# interface_dac_sma_feedback_2PS_LM317.net
KiCad netlist of a schematic drawn in EAGLE
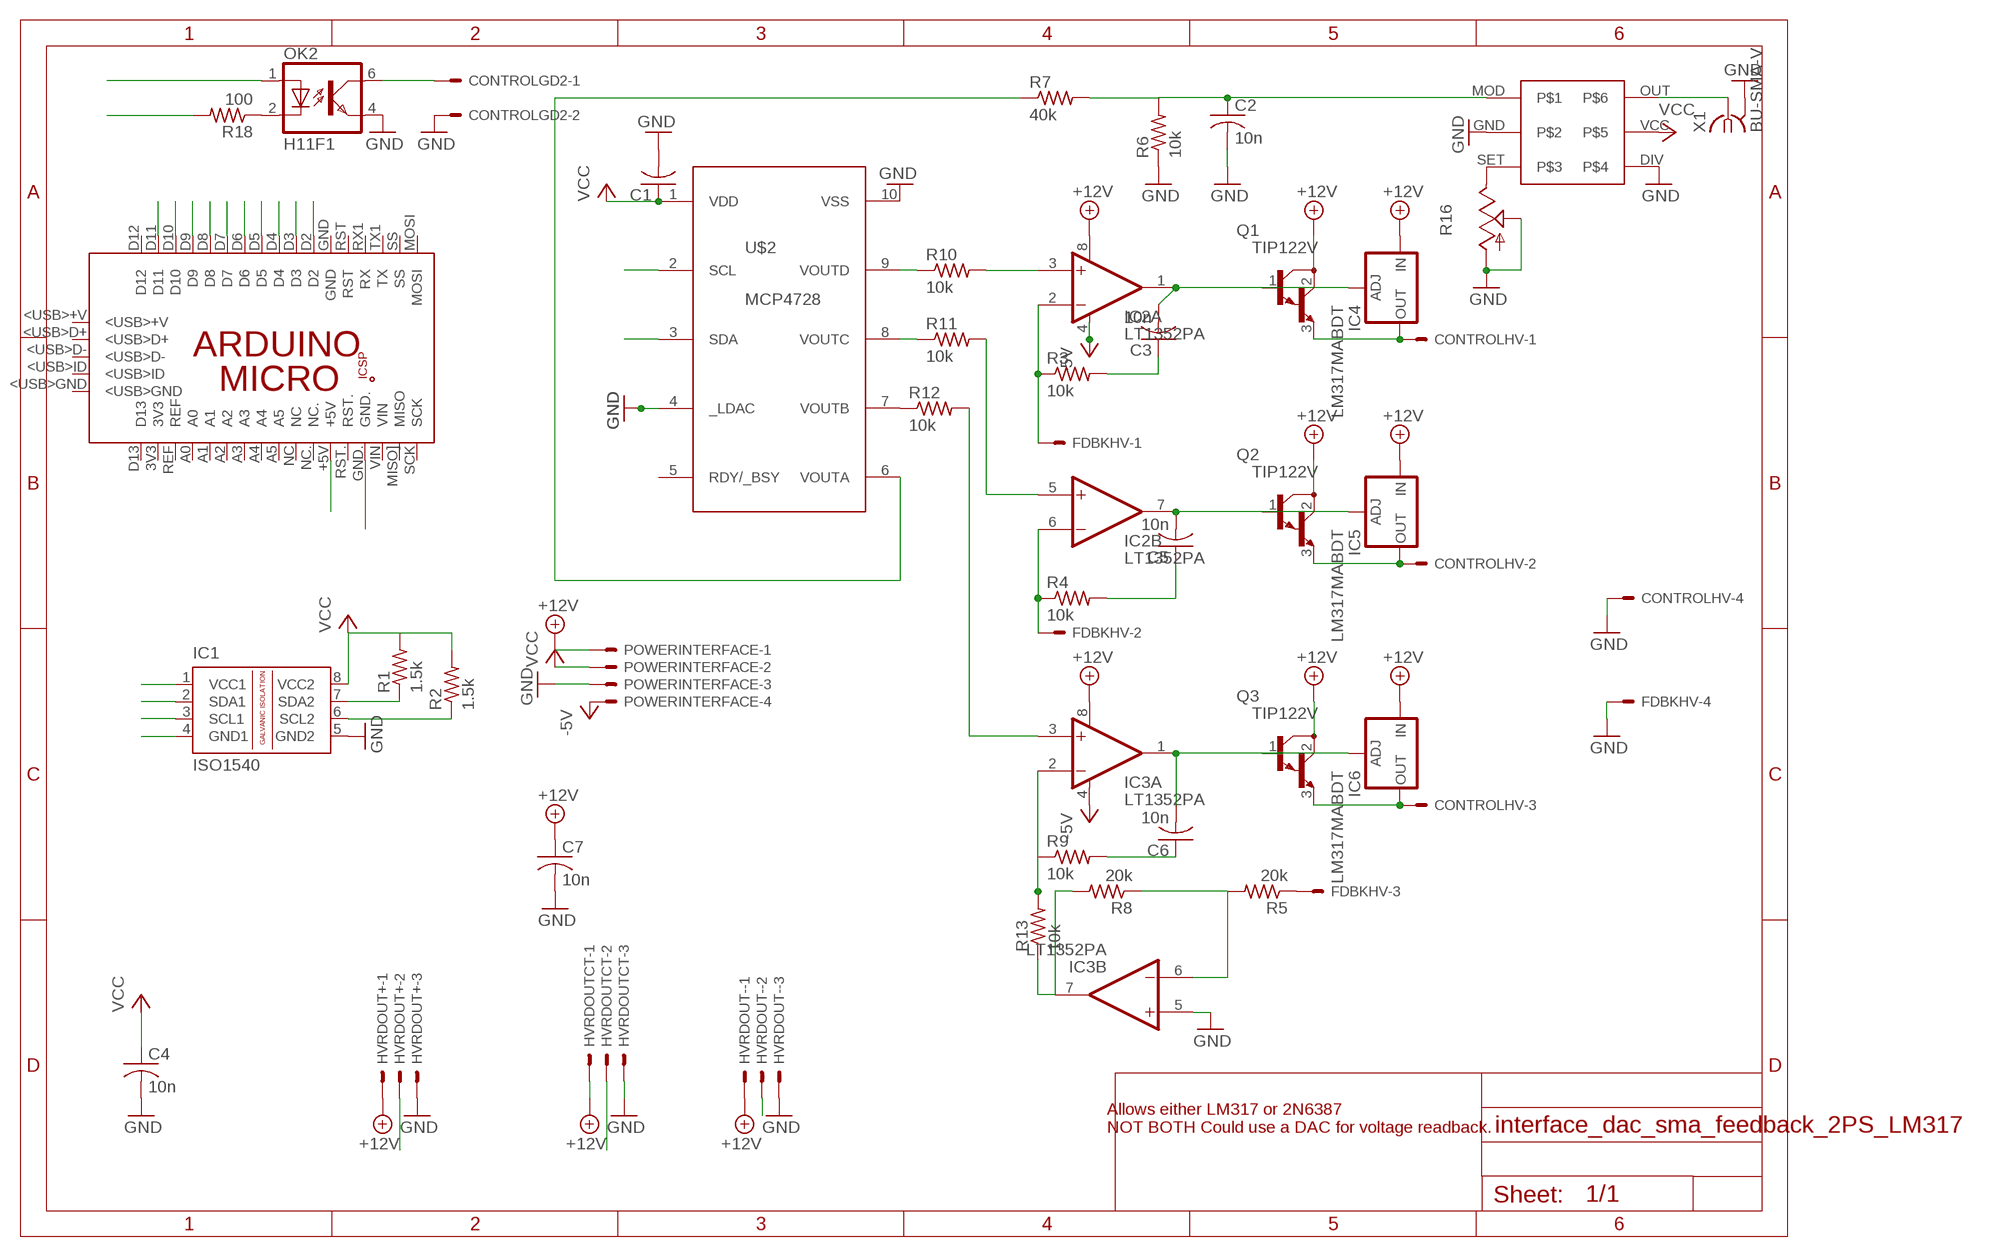
[diagram p0: schematic, sheet 1]

(export (version "E")
  (design (tool "Eeschema 10.0.6"))
  (components
    (comp (ref "C1")
      (value "C-US050-050X075")
      (footprint "eagle-import:C050-050X075")
      (libsource (lib "eagle-import") (part "C-US050-050X075"))
    )
    (comp (ref "C2")
      (value "10n")
      (footprint "eagle-import:C050-024X044")
      (libsource (lib "eagle-import") (part "resistor_C-US050-024X044"))
    )
    (comp (ref "C3")
      (value "10n")
      (footprint "eagle-import:C050-024X044")
      (libsource (lib "eagle-import") (part "resistor_C-US050-024X044"))
    )
    (comp (ref "C4")
      (value "10n")
      (footprint "eagle-import:C075-063X106")
      (libsource (lib "eagle-import") (part "resistor_C-US075-063X106"))
    )
    (comp (ref "C5")
      (value "10n")
      (footprint "eagle-import:C050-024X044")
      (libsource (lib "eagle-import") (part "resistor_C-US050-024X044"))
    )
    (comp (ref "C6")
      (value "10n")
      (footprint "eagle-import:C050-024X044")
      (libsource (lib "eagle-import") (part "resistor_C-US050-024X044"))
    )
    (comp (ref "C7")
      (value "10n")
      (footprint "eagle-import:C050-050X075")
      (libsource (lib "eagle-import") (part "resistor_C-US050-050X075"))
    )
    (comp (ref "CONTROLGD2")
      (value "KK-156-2")
      (footprint "eagle-import:KK-156-2")
      (libsource (lib "eagle-import") (part "KK-156-2"))
    )
    (comp (ref "CONTROLHV")
      (value "KK-156-4")
      (footprint "eagle-import:KK-156-4")
      (libsource (lib "eagle-import") (part "KK-156-4"))
    )
    (comp (ref "FDBKHV")
      (value "KK-156-4")
      (footprint "eagle-import:KK-156-4")
      (libsource (lib "eagle-import") (part "KK-156-4"))
    )
    (comp (ref "HVRDOUT+")
      (value "KK-156-3")
      (footprint "eagle-import:KK-156-3")
      (libsource (lib "eagle-import") (part "KK-156-3"))
    )
    (comp (ref "HVRDOUT-")
      (value "KK-156-3")
      (footprint "eagle-import:KK-156-3")
      (libsource (lib "eagle-import") (part "KK-156-3"))
    )
    (comp (ref "HVRDOUTCT")
      (value "KK-156-3")
      (footprint "eagle-import:KK-156-3")
      (libsource (lib "eagle-import") (part "KK-156-3"))
    )
    (comp (ref "IC1")
      (value "ISO1540")
      (footprint "eagle-import:DIL08")
      (libsource (lib "eagle-import") (part "ISO1540"))
    )
    (comp (ref "IC2")
      (value "LT1352PA")
      (footprint "eagle-import:DIL08")
      (libsource (lib "eagle-import") (part "LT1352PA"))
    )
    (comp (ref "IC3")
      (value "LT1352PA")
      (footprint "eagle-import:DIL08")
      (libsource (lib "eagle-import") (part "LT1352PA"))
    )
    (comp (ref "IC4")
      (value "LM317MABDT")
      (footprint "eagle-import:DPACK")
      (libsource (lib "eagle-import") (part "v-reg_LM317?MABDT"))
    )
    (comp (ref "IC5")
      (value "LM317MABDT")
      (footprint "eagle-import:DPACK")
      (libsource (lib "eagle-import") (part "v-reg_LM317?MABDT"))
    )
    (comp (ref "IC6")
      (value "LM317MABDT")
      (footprint "eagle-import:DPACK")
      (libsource (lib "eagle-import") (part "v-reg_LM317?MABDT"))
    )
    (comp (ref "OK2")
      (value "H11F1")
      (footprint "eagle-import:DIL05")
      (libsource (lib "eagle-import") (part "H11F1"))
    )
    (comp (ref "PCB1")
      (value "ARDUINO_MICRO")
      (footprint "eagle-import:ARDUINO_MICRO")
      (libsource (lib "eagle-import") (part "ARDUINO_MICRO"))
    )
    (comp (ref "POWERINTERFACE")
      (value "KK-156-4")
      (footprint "eagle-import:KK-156-4")
      (libsource (lib "eagle-import") (part "KK-156-4"))
    )
    (comp (ref "Q1")
      (value "TIP122V")
      (footprint "eagle-import:TO220V")
      (libsource (lib "eagle-import") (part "TIP122V"))
    )
    (comp (ref "Q2")
      (value "TIP122V")
      (footprint "eagle-import:TO220V")
      (libsource (lib "eagle-import") (part "TIP122V"))
    )
    (comp (ref "Q3")
      (value "TIP122V")
      (footprint "eagle-import:TO220V")
      (libsource (lib "eagle-import") (part "TIP122V"))
    )
    (comp (ref "R1")
      (value "1.5k")
      (footprint "eagle-import:0207_12")
      (libsource (lib "eagle-import") (part "resistor_R-US_0207/12"))
    )
    (comp (ref "R2")
      (value "1.5k")
      (footprint "eagle-import:0207_12")
      (libsource (lib "eagle-import") (part "resistor_R-US_0207/12"))
    )
    (comp (ref "R3")
      (value "10k")
      (footprint "eagle-import:0207_12")
      (libsource (lib "eagle-import") (part "resistor_R-US_0207/12"))
    )
    (comp (ref "R4")
      (value "10k")
      (footprint "eagle-import:0207_12")
      (libsource (lib "eagle-import") (part "resistor_R-US_0207/12"))
    )
    (comp (ref "R5")
      (value "20k")
      (footprint "eagle-import:0207_12")
      (libsource (lib "eagle-import") (part "resistor_R-US_0207/12"))
    )
    (comp (ref "R6")
      (value "10k")
      (footprint "eagle-import:0207_12")
      (libsource (lib "eagle-import") (part "resistor_R-US_0207/12"))
    )
    (comp (ref "R7")
      (value "40k")
      (footprint "eagle-import:0207_12")
      (libsource (lib "eagle-import") (part "resistor_R-US_0207/12"))
    )
    (comp (ref "R8")
      (value "20k")
      (footprint "eagle-import:0207_12")
      (libsource (lib "eagle-import") (part "resistor_R-US_0207/12"))
    )
    (comp (ref "R9")
      (value "10k")
      (footprint "eagle-import:0207_12")
      (libsource (lib "eagle-import") (part "resistor_R-US_0207/12"))
    )
    (comp (ref "R10")
      (value "10k")
      (footprint "eagle-import:0207_12")
      (libsource (lib "eagle-import") (part "resistor_R-US_0207/12"))
    )
    (comp (ref "R11")
      (value "10k")
      (footprint "eagle-import:0207_12")
      (libsource (lib "eagle-import") (part "resistor_R-US_0207/12"))
    )
    (comp (ref "R12")
      (value "10k")
      (footprint "eagle-import:0207_12")
      (libsource (lib "eagle-import") (part "resistor_R-US_0207/12"))
    )
    (comp (ref "R13")
      (value "10k")
      (footprint "eagle-import:0207_12")
      (libsource (lib "eagle-import") (part "resistor_R-US_0207/12"))
    )
    (comp (ref "R16")
      (value "TRIM_US-B90P")
      (footprint "eagle-import:SP19L")
      (libsource (lib "eagle-import") (part "TRIM_US-B90P"))
    )
    (comp (ref "R18")
      (value "100")
      (footprint "eagle-import:0207_12")
      (libsource (lib "eagle-import") (part "R-US_0207/12"))
    )
    (comp (ref "U$1")
      (value "LTC6992")
      (footprint "eagle-import:DIL06")
      (libsource (lib "eagle-import") (part "LTC6992"))
    )
    (comp (ref "U$2")
      (value "MCP4728DIL")
      (footprint "eagle-import:DIL10")
      (libsource (lib "eagle-import") (part "MCP4728DIL"))
    )
    (comp (ref "X1")
      (value "BU-SMA-V")
      (footprint "eagle-import:BU-SMA-V")
      (libsource (lib "eagle-import") (part "BU-SMA-V"))
    )
  )
  (nets
    (net (code "1") (name "+12V") (class "Default")
      (node (ref "C7") (pin "1") (pinfunction "1_1") (pintype "passive"))
      (node (ref "HVRDOUT+") (pin "1") (pinfunction "S_1") (pintype "passive"))
      (node (ref "HVRDOUT-") (pin "1") (pinfunction "S_1") (pintype "passive"))
      (node (ref "HVRDOUTCT") (pin "1") (pinfunction "S_1") (pintype "passive"))
      (node (ref "IC2") (pin "8") (pinfunction "V+_8") (pintype "power_in"))
      (node (ref "IC3") (pin "8") (pinfunction "V+_8") (pintype "power_in"))
      (node (ref "IC4") (pin "3") (pinfunction "IN_3") (pintype "input"))
      (node (ref "IC5") (pin "3") (pinfunction "IN_3") (pintype "input"))
      (node (ref "IC6") (pin "3") (pinfunction "IN_3") (pintype "input"))
      (node (ref "POWERINTERFACE") (pin "1") (pinfunction "S_1") (pintype "passive"))
      (node (ref "Q1") (pin "2") (pinfunction "C_2") (pintype "passive"))
      (node (ref "Q2") (pin "2") (pinfunction "C_2") (pintype "passive"))
      (node (ref "Q3") (pin "2") (pinfunction "C_2") (pintype "passive"))
    )
    (net (code "2") (name "-5V") (class "Default")
      (node (ref "IC2") (pin "4") (pinfunction "V-_4") (pintype "power_in"))
      (node (ref "IC3") (pin "4") (pinfunction "V-_4") (pintype "power_in"))
      (node (ref "POWERINTERFACE") (pin "4") (pinfunction "S_4") (pintype "passive"))
    )
    (net (code "3") (name "/A+5") (class "Default")
      (node (ref "IC1") (pin "1") (pinfunction "VCC1_1") (pintype "input"))
      (node (ref "PCB1") (pin "+5V") (pinfunction "+5V_+5V") (pintype "bidirectional"))
    )
    (net (code "4") (name "/AGND") (class "Default")
      (node (ref "IC1") (pin "4") (pinfunction "GND1_4") (pintype "input"))
      (node (ref "PCB1") (pin "GND.") (pinfunction "GND._GND.") (pintype "bidirectional"))
      (node (ref "R18") (pin "2") (pinfunction "2_2") (pintype "passive"))
    )
    (net (code "5") (name "/N$2") (class "Default")
      (node (ref "C2") (pin "1") (pinfunction "1_1") (pintype "passive"))
      (node (ref "R6") (pin "2") (pinfunction "2_2") (pintype "passive"))
      (node (ref "R7") (pin "2") (pinfunction "2_2") (pintype "passive"))
      (node (ref "U$1") (pin "MOD") (pinfunction "P$1_MOD") (pintype "bidirectional"))
    )
    (net (code "6") (name "/N$6") (class "Default")
      (node (ref "FDBKHV") (pin "2") (pinfunction "S_2") (pintype "passive"))
      (node (ref "HVRDOUTCT") (pin "2") (pinfunction "S_2") (pintype "passive"))
      (node (ref "IC2") (pin "6") (pinfunction "-IN_6") (pintype "input"))
      (node (ref "R4") (pin "1") (pinfunction "1_1") (pintype "passive"))
    )
    (net (code "7") (name "/N$8") (class "Default")
      (node (ref "FDBKHV") (pin "1") (pinfunction "S_1") (pintype "passive"))
      (node (ref "HVRDOUT+") (pin "2") (pinfunction "S_2") (pintype "passive"))
      (node (ref "IC2") (pin "2") (pinfunction "-IN_2") (pintype "input"))
      (node (ref "R3") (pin "1") (pinfunction "1_1") (pintype "passive"))
    )
    (net (code "8") (name "/N$14") (class "Default")
      (node (ref "HVRDOUT-") (pin "2") (pinfunction "S_2") (pintype "passive"))
      (node (ref "IC3") (pin "7") (pinfunction "OUT_7") (pintype "output"))
      (node (ref "R13") (pin "1") (pinfunction "1_1") (pintype "passive"))
      (node (ref "R8") (pin "2") (pinfunction "2_2") (pintype "passive"))
    )
    (net (code "9") (name "/PWM9") (class "Default")
      (node (ref "OK2") (pin "1") (pinfunction "A_1") (pintype "passive"))
      (node (ref "PCB1") (pin "D9") (pinfunction "D9_D9") (pintype "bidirectional"))
    )
    (net (code "10") (name "/SCL") (class "Default")
      (node (ref "IC1") (pin "3") (pinfunction "SCL1_3") (pintype "input"))
      (node (ref "PCB1") (pin "D3") (pinfunction "D3_D3") (pintype "bidirectional"))
    )
    (net (code "11") (name "/SCL_OUT") (class "Default")
      (node (ref "IC1") (pin "6") (pinfunction "SCL2_6") (pintype "input"))
      (node (ref "R2") (pin "1") (pinfunction "1_1") (pintype "passive"))
      (node (ref "U$2") (pin "2") (pinfunction "SCL_2") (pintype "bidirectional"))
    )
    (net (code "12") (name "/SDA") (class "Default")
      (node (ref "IC1") (pin "2") (pinfunction "SDA1_2") (pintype "input"))
      (node (ref "PCB1") (pin "D2") (pinfunction "D2_D2") (pintype "bidirectional"))
    )
    (net (code "13") (name "/SDA_OUT") (class "Default")
      (node (ref "IC1") (pin "7") (pinfunction "SDA2_7") (pintype "input"))
      (node (ref "R1") (pin "1") (pinfunction "1_1") (pintype "passive"))
      (node (ref "U$2") (pin "3") (pinfunction "SDA_3") (pintype "bidirectional"))
    )
    (net (code "14") (name "GND") (class "Default")
      (node (ref "C1") (pin "2") (pinfunction "2_2") (pintype "passive"))
      (node (ref "C2") (pin "2") (pinfunction "2_2") (pintype "passive"))
      (node (ref "C4") (pin "2") (pinfunction "2_2") (pintype "passive"))
      (node (ref "C7") (pin "2") (pinfunction "2_2") (pintype "passive"))
      (node (ref "CONTROLGD2") (pin "2") (pinfunction "S_2") (pintype "passive"))
      (node (ref "CONTROLHV") (pin "4") (pinfunction "S_4") (pintype "passive"))
      (node (ref "FDBKHV") (pin "4") (pinfunction "S_4") (pintype "passive"))
      (node (ref "HVRDOUT+") (pin "3") (pinfunction "S_3") (pintype "passive"))
      (node (ref "HVRDOUT-") (pin "3") (pinfunction "S_3") (pintype "passive"))
      (node (ref "HVRDOUTCT") (pin "3") (pinfunction "S_3") (pintype "passive"))
      (node (ref "IC1") (pin "5") (pinfunction "GND2_5") (pintype "input"))
      (node (ref "IC3") (pin "5") (pinfunction "+IN_5") (pintype "input"))
      (node (ref "OK2") (pin "4") (pinfunction "EMIT_4") (pintype "passive"))
      (node (ref "POWERINTERFACE") (pin "3") (pinfunction "S_3") (pintype "passive"))
      (node (ref "R16") (pin "A") (pinfunction "A_A") (pintype "passive"))
      (node (ref "R16") (pin "S") (pinfunction "S_S") (pintype "passive"))
      (node (ref "R6") (pin "1") (pinfunction "1_1") (pintype "passive"))
      (node (ref "U$1") (pin "DIV") (pinfunction "P$4_DIV") (pintype "bidirectional"))
      (node (ref "U$1") (pin "GND") (pinfunction "P$2_GND") (pintype "bidirectional"))
      (node (ref "U$2") (pin "10") (pinfunction "VSS_10") (pintype "bidirectional"))
      (node (ref "U$2") (pin "4") (pinfunction "_LDAC_4") (pintype "bidirectional"))
      (node (ref "X1") (pin "2") (pinfunction "2_2") (pintype "passive"))
      (node (ref "X1") (pin "3") (pinfunction "2_3") (pintype "passive"))
      (node (ref "X1") (pin "4") (pinfunction "2_4") (pintype "passive"))
      (node (ref "X1") (pin "5") (pinfunction "2_5") (pintype "passive"))
    )
    (net (code "15") (name "Net-(C3-Pad1)") (class "Default")
      (node (ref "C3") (pin "1") (pinfunction "1_1") (pintype "passive"))
      (node (ref "R3") (pin "2") (pinfunction "2_2") (pintype "passive"))
    )
    (net (code "16") (name "Net-(C5-Pad1)") (class "Default")
      (node (ref "C5") (pin "1") (pinfunction "1_1") (pintype "passive"))
      (node (ref "R4") (pin "2") (pinfunction "2_2") (pintype "passive"))
    )
    (net (code "17") (name "Net-(C6-Pad1)") (class "Default")
      (node (ref "C6") (pin "1") (pinfunction "1_1") (pintype "passive"))
      (node (ref "R9") (pin "2") (pinfunction "2_2") (pintype "passive"))
    )
    (net (code "18") (name "Net-(CONTROLGD2A-S)") (class "Default")
      (node (ref "CONTROLGD2") (pin "1") (pinfunction "S_1") (pintype "passive"))
      (node (ref "OK2") (pin "6") (pinfunction "COL_6") (pintype "passive"))
    )
    (net (code "19") (name "Net-(CONTROLHVA-S)") (class "Default")
      (node (ref "CONTROLHV") (pin "1") (pinfunction "S_1") (pintype "passive"))
      (node (ref "IC4") (pin "4") (pinfunction "OUT_4") (pintype "passive"))
      (node (ref "Q1") (pin "3") (pinfunction "E_3") (pintype "passive"))
    )
    (net (code "20") (name "Net-(CONTROLHVB-S)") (class "Default")
      (node (ref "CONTROLHV") (pin "2") (pinfunction "S_2") (pintype "passive"))
      (node (ref "IC5") (pin "4") (pinfunction "OUT_4") (pintype "passive"))
      (node (ref "Q2") (pin "3") (pinfunction "E_3") (pintype "passive"))
    )
    (net (code "21") (name "Net-(CONTROLHVC-S)") (class "Default")
      (node (ref "CONTROLHV") (pin "3") (pinfunction "S_3") (pintype "passive"))
      (node (ref "IC6") (pin "4") (pinfunction "OUT_4") (pintype "passive"))
      (node (ref "Q3") (pin "3") (pinfunction "E_3") (pintype "passive"))
    )
    (net (code "22") (name "Net-(FDBKHVC-S)") (class "Default")
      (node (ref "FDBKHV") (pin "3") (pinfunction "S_3") (pintype "passive"))
      (node (ref "R5") (pin "1") (pinfunction "1_1") (pintype "passive"))
    )
    (net (code "23") (name "Net-(IC2A-+IN)") (class "Default")
      (node (ref "IC2") (pin "3") (pinfunction "+IN_3") (pintype "input"))
      (node (ref "R10") (pin "2") (pinfunction "2_2") (pintype "passive"))
    )
    (net (code "24") (name "Net-(IC2A-OUT)") (class "Default")
      (node (ref "C3") (pin "2") (pinfunction "2_2") (pintype "passive"))
      (node (ref "IC2") (pin "1") (pinfunction "OUT_1") (pintype "output"))
      (node (ref "IC4") (pin "1") (pinfunction "ADJ_1") (pintype "input"))
      (node (ref "Q1") (pin "1") (pinfunction "B_1") (pintype "passive"))
    )
    (net (code "25") (name "Net-(IC2B-+IN)") (class "Default")
      (node (ref "IC2") (pin "5") (pinfunction "+IN_5") (pintype "input"))
      (node (ref "R11") (pin "2") (pinfunction "2_2") (pintype "passive"))
    )
    (net (code "26") (name "Net-(IC2B-OUT)") (class "Default")
      (node (ref "C5") (pin "2") (pinfunction "2_2") (pintype "passive"))
      (node (ref "IC2") (pin "7") (pinfunction "OUT_7") (pintype "output"))
      (node (ref "IC5") (pin "1") (pinfunction "ADJ_1") (pintype "input"))
      (node (ref "Q2") (pin "1") (pinfunction "B_1") (pintype "passive"))
    )
    (net (code "27") (name "Net-(IC3A-+IN)") (class "Default")
      (node (ref "IC3") (pin "3") (pinfunction "+IN_3") (pintype "input"))
      (node (ref "R12") (pin "2") (pinfunction "2_2") (pintype "passive"))
    )
    (net (code "28") (name "Net-(IC3A--IN)") (class "Default")
      (node (ref "IC3") (pin "2") (pinfunction "-IN_2") (pintype "input"))
      (node (ref "R13") (pin "2") (pinfunction "2_2") (pintype "passive"))
      (node (ref "R9") (pin "1") (pinfunction "1_1") (pintype "passive"))
    )
    (net (code "29") (name "Net-(IC3A-OUT)") (class "Default")
      (node (ref "C6") (pin "2") (pinfunction "2_2") (pintype "passive"))
      (node (ref "IC3") (pin "1") (pinfunction "OUT_1") (pintype "output"))
      (node (ref "IC6") (pin "1") (pinfunction "ADJ_1") (pintype "input"))
      (node (ref "Q3") (pin "1") (pinfunction "B_1") (pintype "passive"))
    )
    (net (code "30") (name "Net-(IC3B--IN)") (class "Default")
      (node (ref "IC3") (pin "6") (pinfunction "-IN_6") (pintype "input"))
      (node (ref "R5") (pin "2") (pinfunction "2_2") (pintype "passive"))
      (node (ref "R8") (pin "1") (pinfunction "1_1") (pintype "passive"))
    )
    (net (code "31") (name "Net-(OK2-C)") (class "Default")
      (node (ref "OK2") (pin "2") (pinfunction "C_2") (pintype "passive"))
      (node (ref "R18") (pin "1") (pinfunction "1_1") (pintype "passive"))
    )
    (net (code "32") (name "Net-(U$1-P$3)") (class "Default")
      (node (ref "R16") (pin "E") (pinfunction "E_E") (pintype "passive"))
      (node (ref "U$1") (pin "SET") (pinfunction "P$3_SET") (pintype "bidirectional"))
    )
    (net (code "33") (name "Net-(U$1-P$6)") (class "Default")
      (node (ref "U$1") (pin "OUT") (pinfunction "P$6_OUT") (pintype "bidirectional"))
      (node (ref "X1") (pin "1") (pinfunction "1_1") (pintype "passive"))
    )
    (net (code "34") (name "Net-(U$2-VOUTA)") (class "Default")
      (node (ref "R7") (pin "1") (pinfunction "1_1") (pintype "passive"))
      (node (ref "U$2") (pin "6") (pinfunction "VOUTA_6") (pintype "bidirectional"))
    )
    (net (code "35") (name "Net-(U$2-VOUTB)") (class "Default")
      (node (ref "R12") (pin "1") (pinfunction "1_1") (pintype "passive"))
      (node (ref "U$2") (pin "7") (pinfunction "VOUTB_7") (pintype "bidirectional"))
    )
    (net (code "36") (name "Net-(U$2-VOUTC)") (class "Default")
      (node (ref "R11") (pin "1") (pinfunction "1_1") (pintype "passive"))
      (node (ref "U$2") (pin "8") (pinfunction "VOUTC_8") (pintype "bidirectional"))
    )
    (net (code "37") (name "Net-(U$2-VOUTD)") (class "Default")
      (node (ref "R10") (pin "1") (pinfunction "1_1") (pintype "passive"))
      (node (ref "U$2") (pin "9") (pinfunction "VOUTD_9") (pintype "bidirectional"))
    )
    (net (code "38") (name "VCC") (class "Default")
      (node (ref "C1") (pin "1") (pinfunction "1_1") (pintype "passive"))
      (node (ref "C4") (pin "1") (pinfunction "1_1") (pintype "passive"))
      (node (ref "IC1") (pin "8") (pinfunction "VCC2_8") (pintype "input"))
      (node (ref "POWERINTERFACE") (pin "2") (pinfunction "S_2") (pintype "passive"))
      (node (ref "R1") (pin "2") (pinfunction "2_2") (pintype "passive"))
      (node (ref "R2") (pin "2") (pinfunction "2_2") (pintype "passive"))
      (node (ref "U$1") (pin "VCC") (pinfunction "P$5_VCC") (pintype "bidirectional"))
      (node (ref "U$2") (pin "1") (pinfunction "VDD_1") (pintype "bidirectional"))
    )
    (net (code "39") (name "unconnected-(PCB1-MISO-PadMISO])") (class "Default")
      (node (ref "PCB1") (pin "MISO]") (pinfunction "MISO_MISO]") (pintype "bidirectional"))
    )
    (net (code "40") (name "unconnected-(PCB1-Pad3V3)") (class "Default")
      (node (ref "PCB1") (pin "3V3") (pinfunction "3V3_3V3") (pintype "bidirectional"))
    )
    (net (code "41") (name "unconnected-(PCB1-Pad5V)") (class "Default")
      (node (ref "PCB1") (pin "5V") (pinfunction "5V_5V") (pintype "bidirectional"))
    )
    (net (code "42") (name "unconnected-(PCB1-Pad<USB>+V)") (class "Default")
      (node (ref "PCB1") (pin "<USB>+V") (pinfunction "<USB>+V_<USB>+V") (pintype "bidirectional"))
    )
    (net (code "43") (name "unconnected-(PCB1-Pad<USB>D+)") (class "Default")
      (node (ref "PCB1") (pin "<USB>D+") (pinfunction "<USB>D+_<USB>D+") (pintype "bidirectional"))
    )
    (net (code "44") (name "unconnected-(PCB1-Pad<USB>D-)") (class "Default")
      (node (ref "PCB1") (pin "<USB>D-") (pinfunction "<USB>D-_<USB>D-") (pintype "bidirectional"))
    )
    (net (code "45") (name "unconnected-(PCB1-Pad<USB>GND)") (class "Default")
      (node (ref "PCB1") (pin "<USB>GND") (pinfunction "<USB>GND_<USB>GND") (pintype "bidirectional"))
    )
    (net (code "46") (name "unconnected-(PCB1-Pad<USB>ID)") (class "Default")
      (node (ref "PCB1") (pin "<USB>ID") (pinfunction "<USB>ID_<USB>ID") (pintype "bidirectional"))
    )
    (net (code "47") (name "unconnected-(PCB1-PadA0)") (class "Default")
      (node (ref "PCB1") (pin "A0") (pinfunction "A0_A0") (pintype "bidirectional"))
    )
    (net (code "48") (name "unconnected-(PCB1-PadA1)") (class "Default")
      (node (ref "PCB1") (pin "A1") (pinfunction "A1_A1") (pintype "bidirectional"))
    )
    (net (code "49") (name "unconnected-(PCB1-PadA2)") (class "Default")
      (node (ref "PCB1") (pin "A2") (pinfunction "A2_A2") (pintype "bidirectional"))
    )
    (net (code "50") (name "unconnected-(PCB1-PadA3)") (class "Default")
      (node (ref "PCB1") (pin "A3") (pinfunction "A3_A3") (pintype "bidirectional"))
    )
    (net (code "51") (name "unconnected-(PCB1-PadA4)") (class "Default")
      (node (ref "PCB1") (pin "A4") (pinfunction "A4_A4") (pintype "bidirectional"))
    )
    (net (code "52") (name "unconnected-(PCB1-PadA5)") (class "Default")
      (node (ref "PCB1") (pin "A5") (pinfunction "A5_A5") (pintype "bidirectional"))
    )
    (net (code "53") (name "unconnected-(PCB1-PadD4)") (class "Default")
      (node (ref "PCB1") (pin "D4") (pinfunction "D4_D4") (pintype "bidirectional"))
    )
    (net (code "54") (name "unconnected-(PCB1-PadD5)") (class "Default")
      (node (ref "PCB1") (pin "D5") (pinfunction "D5_D5") (pintype "bidirectional"))
    )
    (net (code "55") (name "unconnected-(PCB1-PadD6)") (class "Default")
      (node (ref "PCB1") (pin "D6") (pinfunction "D6_D6") (pintype "bidirectional"))
    )
    (net (code "56") (name "unconnected-(PCB1-PadD7)") (class "Default")
      (node (ref "PCB1") (pin "D7") (pinfunction "D7_D7") (pintype "bidirectional"))
    )
    (net (code "57") (name "unconnected-(PCB1-PadD8)") (class "Default")
      (node (ref "PCB1") (pin "D8") (pinfunction "D8_D8") (pintype "bidirectional"))
    )
    (net (code "58") (name "unconnected-(PCB1-PadD10)") (class "Default")
      (node (ref "PCB1") (pin "D10") (pinfunction "D10_D10") (pintype "bidirectional"))
    )
    (net (code "59") (name "unconnected-(PCB1-PadD11)") (class "Default")
      (node (ref "PCB1") (pin "D11") (pinfunction "D11_D11") (pintype "bidirectional"))
    )
    (net (code "60") (name "unconnected-(PCB1-PadD12)") (class "Default")
      (node (ref "PCB1") (pin "D12") (pinfunction "D12_D12") (pintype "bidirectional"))
    )
    (net (code "61") (name "unconnected-(PCB1-PadD13)") (class "Default")
      (node (ref "PCB1") (pin "D13") (pinfunction "D13_D13") (pintype "bidirectional"))
    )
    (net (code "62") (name "unconnected-(PCB1-PadGND)") (class "Default")
      (node (ref "PCB1") (pin "GND") (pinfunction "GND_GND") (pintype "bidirectional"))
    )
    (net (code "63") (name "unconnected-(PCB1-PadGND_)") (class "Default")
      (node (ref "PCB1") (pin "GND_") (pinfunction "GND__GND_") (pintype "bidirectional"))
    )
    (net (code "64") (name "unconnected-(PCB1-PadMISO.)") (class "Default")
      (node (ref "PCB1") (pin "MISO.") (pinfunction "MISO._MISO.") (pintype "bidirectional"))
    )
    (net (code "65") (name "unconnected-(PCB1-PadMOSI)") (class "Default")
      (node (ref "PCB1") (pin "MOSI") (pinfunction "MOSI_MOSI") (pintype "bidirectional"))
    )
    (net (code "66") (name "unconnected-(PCB1-PadMOSI.)") (class "Default")
      (node (ref "PCB1") (pin "MOSI.") (pinfunction "MOSI._MOSI.") (pintype "bidirectional"))
    )
    (net (code "67") (name "unconnected-(PCB1-PadNC)") (class "Default")
      (node (ref "PCB1") (pin "NC") (pinfunction "NC_NC") (pintype "bidirectional"))
    )
    (net (code "68") (name "unconnected-(PCB1-PadNC.)") (class "Default")
      (node (ref "PCB1") (pin "NC.") (pinfunction "NC._NC.") (pintype "bidirectional"))
    )
    (net (code "69") (name "unconnected-(PCB1-PadREF)") (class "Default")
      (node (ref "PCB1") (pin "REF") (pinfunction "REF_REF") (pintype "bidirectional"))
    )
    (net (code "70") (name "unconnected-(PCB1-PadRESET..)") (class "Default")
      (node (ref "PCB1") (pin "RESET..") (pinfunction "RESET.._RESET..") (pintype "bidirectional"))
    )
    (net (code "71") (name "unconnected-(PCB1-PadRST)") (class "Default")
      (node (ref "PCB1") (pin "RST") (pinfunction "RST_RST") (pintype "bidirectional"))
    )
    (net (code "72") (name "unconnected-(PCB1-PadRST.)") (class "Default")
      (node (ref "PCB1") (pin "RST.") (pinfunction "RST._RST.") (pintype "bidirectional"))
    )
    (net (code "73") (name "unconnected-(PCB1-PadSCK)") (class "Default")
      (node (ref "PCB1") (pin "SCK") (pinfunction "SCK_SCK") (pintype "bidirectional"))
    )
    (net (code "74") (name "unconnected-(PCB1-PadSCK.)") (class "Default")
      (node (ref "PCB1") (pin "SCK.") (pinfunction "SCK._SCK.") (pintype "bidirectional"))
    )
    (net (code "75") (name "unconnected-(PCB1-PadSS)") (class "Default")
      (node (ref "PCB1") (pin "SS") (pinfunction "SS_SS") (pintype "bidirectional"))
    )
    (net (code "76") (name "unconnected-(PCB1-PadVIN)") (class "Default")
      (node (ref "PCB1") (pin "VIN") (pinfunction "VIN_VIN") (pintype "bidirectional"))
    )
    (net (code "77") (name "unconnected-(PCB1-RX-PadRX1)") (class "Default")
      (node (ref "PCB1") (pin "RX1") (pinfunction "RX_RX1") (pintype "bidirectional"))
    )
    (net (code "78") (name "unconnected-(PCB1-TX-PadTX1)") (class "Default")
      (node (ref "PCB1") (pin "TX1") (pinfunction "TX_TX1") (pintype "bidirectional"))
    )
    (net (code "79") (name "unconnected-(U$2-RDY{slash}_BSY-Pad5)") (class "Default")
      (node (ref "U$2") (pin "5") (pinfunction "RDY/_BSY_5") (pintype "bidirectional"))
    )
  )
)
